# Buck.net
KiCad netlist of a schematic drawn in Altium Designer
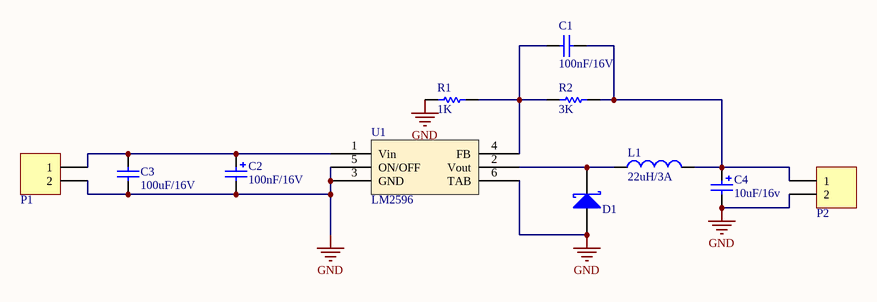
[diagram p0: Buck.SchDoc]

(export (version "E")
  (design (tool "Eeschema 10.0.6"))
  (components
    (comp (ref "C1")
      (value "100nF/16V")
      (footprint "CAP-SM-0603")
      (description "Capacitor")
      (fields (field (name "Comment") "Cap Non-Pol SMD"))
      (libsource (lib "PIF_Library") (part "Cap Non-Pol SMD"))
    )
    (comp (ref "C2")
      (value "100nF/16V")
      (footprint "CP1.5/3.4")
      (description "Polarized Capacitor (Radial)")
      (fields (field (name "Comment") "Cap Pol"))
      (libsource (lib "PIF_Library") (part "Cap Pol"))
    )
    (comp (ref "C3")
      (value "100uF/16V")
      (footprint "CAP-SM-0603")
      (description "Capacitor")
      (fields (field (name "Comment") "Cap Non-Pol SMD"))
      (libsource (lib "PIF_Library") (part "Cap Non-Pol SMD"))
    )
    (comp (ref "C4")
      (value "10uF/16v")
      (footprint "CP1.5/3.4")
      (description "Polarized Capacitor (Radial)")
      (fields (field (name "Comment") "Cap Pol"))
      (libsource (lib "PIF_Library") (part "Cap Pol"))
    )
    (comp (ref "D1")
      (value "D Schottky")
      (footprint "SS34")
      (description "Schottky Diode")
      (fields (field (name "PUBLISHER") "Altium Limited"))
      (libsource (lib "PIF_Library") (part "D Schottky"))
    )
    (comp (ref "L1")
      (value "22uH/3A")
      (footprint "INDUCTOR 12.5x12.5")
      (description "Inductor")
      (libsource (lib "PIF_Library") (part "Inductor"))
    )
    (comp (ref "P1")
      (value "Domino 2")
      (footprint "DOMINO 2- 5mm")
      (description "Domino, 2-Pin")
      (fields (field (name "PUBLISHER") "Altium Limited"))
      (libsource (lib "") (part "Domino 2_1"))
    )
    (comp (ref "P2")
      (value "Domino 2")
      (footprint "DOMINO 2- 5mm")
      (description "Domino, 2-Pin")
      (fields (field (name "PUBLISHER") "Altium Limited"))
      (libsource (lib "PIF_Library") (part "Domino 2"))
    )
    (comp (ref "R1")
      (value "1K")
      (footprint "RES-SM-0603")
      (description "Resistor")
      (fields (field (name "Comment") "RESISTOR SMD"))
      (libsource (lib "PIF_Library") (part "RESISTOR SMD"))
    )
    (comp (ref "R2")
      (value "3K")
      (footprint "RES-SM-0603")
      (description "Resistor")
      (fields (field (name "Comment") "RESISTOR SMD"))
      (libsource (lib "PIF_Library") (part "RESISTOR SMD"))
    )
    (comp (ref "U1")
      (value "LM2596")
      (footprint "LM2596")
      (description "SMD")
      (libsource (lib "buck_boost") (part "LM2596"))
    )
  )
  (nets
    (net (code "1") (name "GND") (class "Default")
      (node (ref "C2") (pin "2") (pinfunction "2_2") (pintype "passive"))
      (node (ref "C3") (pin "1") (pinfunction "1_1") (pintype "passive"))
      (node (ref "C4") (pin "2") (pinfunction "2_2") (pintype "passive"))
      (node (ref "D1") (pin "1") (pinfunction "A_1") (pintype "passive"))
      (node (ref "P1") (pin "2") (pinfunction "2_2") (pintype "passive"))
      (node (ref "P2") (pin "2") (pinfunction "2_2") (pintype "passive"))
      (node (ref "R1") (pin "1") (pinfunction "1_1") (pintype "passive"))
      (node (ref "U1") (pin "3") (pinfunction "GND_3") (pintype "passive"))
      (node (ref "U1") (pin "5") (pinfunction "ON/OFF_5") (pintype "passive"))
      (node (ref "U1") (pin "6") (pinfunction "TAB_6") (pintype "passive"))
    )
    (net (code "2") (name "Net-(C1-Pad2)") (class "Default")
      (node (ref "C1") (pin "2") (pinfunction "2_2") (pintype "passive"))
      (node (ref "C4") (pin "1") (pinfunction "1_1") (pintype "passive"))
      (node (ref "L1") (pin "2") (pinfunction "2_2") (pintype "passive"))
      (node (ref "P2") (pin "1") (pinfunction "1_1") (pintype "passive"))
      (node (ref "R2") (pin "2") (pinfunction "2_2") (pintype "passive"))
    )
    (net (code "3") (name "Net-(D1-K)") (class "Default")
      (node (ref "D1") (pin "2") (pinfunction "K_2") (pintype "passive"))
      (node (ref "L1") (pin "1") (pinfunction "1_1") (pintype "passive"))
      (node (ref "U1") (pin "2") (pinfunction "Vout_2") (pintype "passive"))
    )
    (net (code "4") (name "Net-(U1-FB)") (class "Default")
      (node (ref "C1") (pin "1") (pinfunction "1_1") (pintype "passive"))
      (node (ref "R1") (pin "2") (pinfunction "2_2") (pintype "passive"))
      (node (ref "R2") (pin "1") (pinfunction "1_1") (pintype "passive"))
      (node (ref "U1") (pin "4") (pinfunction "FB_4") (pintype "passive"))
    )
    (net (code "5") (name "Net-(U1-Vin)") (class "Default")
      (node (ref "C2") (pin "1") (pinfunction "1_1") (pintype "passive"))
      (node (ref "C3") (pin "2") (pinfunction "2_2") (pintype "passive"))
      (node (ref "P1") (pin "1") (pinfunction "1_1") (pintype "passive"))
      (node (ref "U1") (pin "1") (pinfunction "Vin_1") (pintype "passive"))
    )
  )
)
